# micro3.net
KiCad netlist of a schematic drawn in EAGLE
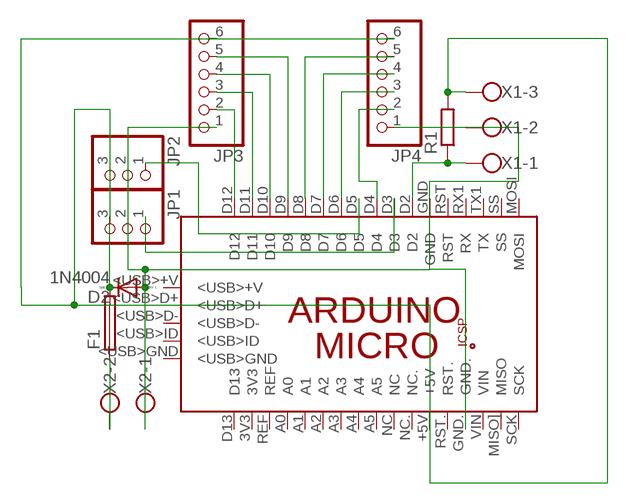
[diagram p0: schematic, sheet 1]

(export (version "E")
  (design (tool "Eeschema 10.0.6"))
  (components
    (comp (ref "D2")
      (value "1N4004")
      (footprint "eagle-import:DO41-10")
      (libsource (lib "eagle-import") (part "1N4004"))
    )
    (comp (ref "F1")
      (value "GSH15")
      (footprint "eagle-import:GSH15")
      (fields (field (name "MPN") "64900001039"))
      (libsource (lib "eagle-import") (part "GSH15"))
    )
    (comp (ref "JP1")
      (value "PINHD-1X3")
      (footprint "eagle-import:1X03")
      (libsource (lib "eagle-import") (part "PINHD-1X3"))
    )
    (comp (ref "JP2")
      (value "PINHD-1X3")
      (footprint "eagle-import:1X03")
      (libsource (lib "eagle-import") (part "PINHD-1X3"))
    )
    (comp (ref "JP3")
      (value "PINHD-1X6")
      (footprint "eagle-import:1X06")
      (libsource (lib "eagle-import") (part "PINHD-1X6"))
    )
    (comp (ref "JP4")
      (value "PINHD-1X6")
      (footprint "eagle-import:1X06")
      (libsource (lib "eagle-import") (part "PINHD-1X6"))
    )
    (comp (ref "PCB1")
      (value "ARDUINO_MICRO")
      (footprint "eagle-import:ARDUINO_MICRO")
      (libsource (lib "eagle-import") (part "ARDUINO_MICRO"))
    )
    (comp (ref "R1")
      (value "R-EU_0207/15")
      (footprint "eagle-import:0207_15")
      (libsource (lib "eagle-import") (part "R-EU_0207/15"))
    )
    (comp (ref "X1")
      (value "W237-103")
      (footprint "eagle-import:W237-103")
      (fields (field (name "MPN") "237-103"))
      (libsource (lib "eagle-import") (part "W237-103"))
    )
    (comp (ref "X2")
      (value "W237-102")
      (footprint "eagle-import:W237-102")
      (fields (field (name "MPN") "237-102"))
      (libsource (lib "eagle-import") (part "W237-102"))
    )
  )
  (nets
    (net (code "1") (name "Net-(JP1-Pad1)") (class "Default")
      (node (ref "JP1") (pin "1") (pinfunction "1_1") (pintype "passive"))
      (node (ref "PCB1") (pin "D3") (pinfunction "D3_D3") (pintype "bidirectional"))
    )
    (net (code "2") (name "Net-(JP2-Pad1)") (class "Default")
      (node (ref "JP2") (pin "1") (pinfunction "1_1") (pintype "passive"))
      (node (ref "PCB1") (pin "D5") (pinfunction "D5_D5") (pintype "bidirectional"))
    )
    (net (code "3") (name "Net-(JP3-Pad2)") (class "Default")
      (node (ref "JP3") (pin "2") (pinfunction "2_2") (pintype "passive"))
      (node (ref "PCB1") (pin "D12") (pinfunction "D12_D12") (pintype "bidirectional"))
    )
    (net (code "4") (name "Net-(JP3-Pad3)") (class "Default")
      (node (ref "JP3") (pin "3") (pinfunction "3_3") (pintype "passive"))
      (node (ref "PCB1") (pin "D11") (pinfunction "D11_D11") (pintype "bidirectional"))
    )
    (net (code "5") (name "Net-(JP3-Pad4)") (class "Default")
      (node (ref "JP3") (pin "4") (pinfunction "4_4") (pintype "passive"))
      (node (ref "PCB1") (pin "D10") (pinfunction "D10_D10") (pintype "bidirectional"))
    )
    (net (code "6") (name "Net-(JP3-Pad5)") (class "Default")
      (node (ref "JP3") (pin "5") (pinfunction "5_5") (pintype "passive"))
      (node (ref "PCB1") (pin "D9") (pinfunction "D9_D9") (pintype "bidirectional"))
    )
    (net (code "7") (name "Net-(JP4-Pad2)") (class "Default")
      (node (ref "JP4") (pin "2") (pinfunction "2_2") (pintype "passive"))
      (node (ref "PCB1") (pin "D4") (pinfunction "D4_D4") (pintype "bidirectional"))
    )
    (net (code "8") (name "Net-(JP4-Pad3)") (class "Default")
      (node (ref "JP4") (pin "3") (pinfunction "3_3") (pintype "passive"))
      (node (ref "PCB1") (pin "D6") (pinfunction "D6_D6") (pintype "bidirectional"))
    )
    (net (code "9") (name "Net-(JP4-Pad4)") (class "Default")
      (node (ref "JP4") (pin "4") (pinfunction "4_4") (pintype "passive"))
      (node (ref "PCB1") (pin "D7") (pinfunction "D7_D7") (pintype "bidirectional"))
    )
    (net (code "10") (name "Net-(JP4-Pad5)") (class "Default")
      (node (ref "JP4") (pin "5") (pinfunction "5_5") (pintype "passive"))
      (node (ref "PCB1") (pin "D8") (pinfunction "D8_D8") (pintype "bidirectional"))
    )
    (net (code "11") (name "Net-(X1A-KL)") (class "Default")
      (node (ref "PCB1") (pin "D2") (pinfunction "D2_D2") (pintype "bidirectional"))
      (node (ref "R1") (pin "1") (pinfunction "1_1") (pintype "passive"))
      (node (ref "X1") (pin "1") (pinfunction "KL_1") (pintype "passive"))
    )
    (net (code "12") (name "Net-(X1B-KL)") (class "Default")
      (node (ref "D2") (pin "A") (pinfunction "A_A") (pintype "passive"))
      (node (ref "JP1") (pin "2") (pinfunction "2_2") (pintype "passive"))
      (node (ref "JP2") (pin "2") (pinfunction "2_2") (pintype "passive"))
      (node (ref "JP3") (pin "1") (pinfunction "1_1") (pintype "passive"))
      (node (ref "JP4") (pin "1") (pinfunction "1_1") (pintype "passive"))
      (node (ref "PCB1") (pin "GND") (pinfunction "GND_GND") (pintype "bidirectional"))
      (node (ref "PCB1") (pin "GND.") (pinfunction "GND._GND.") (pintype "bidirectional"))
      (node (ref "X1") (pin "2") (pinfunction "KL_2") (pintype "passive"))
      (node (ref "X2") (pin "1") (pinfunction "KL_1") (pintype "passive"))
    )
    (net (code "13") (name "Net-(X1C-KL)") (class "Default")
      (node (ref "D2") (pin "C") (pinfunction "C_C") (pintype "passive"))
      (node (ref "F1") (pin "2") (pinfunction "2_2") (pintype "passive"))
      (node (ref "JP1") (pin "3") (pinfunction "3_3") (pintype "passive"))
      (node (ref "JP2") (pin "3") (pinfunction "3_3") (pintype "passive"))
      (node (ref "JP3") (pin "6") (pinfunction "6_6") (pintype "passive"))
      (node (ref "JP4") (pin "6") (pinfunction "6_6") (pintype "passive"))
      (node (ref "PCB1") (pin "+5V") (pinfunction "+5V_+5V") (pintype "bidirectional"))
      (node (ref "R1") (pin "2") (pinfunction "2_2") (pintype "passive"))
      (node (ref "X1") (pin "3") (pinfunction "KL_3") (pintype "passive"))
    )
    (net (code "14") (name "Net-(X2B-KL)") (class "Default")
      (node (ref "F1") (pin "1") (pinfunction "1_1") (pintype "passive"))
      (node (ref "X2") (pin "2") (pinfunction "KL_2") (pintype "passive"))
    )
    (net (code "15") (name "unconnected-(PCB1-MISO-PadMISO])") (class "Default")
      (node (ref "PCB1") (pin "MISO]") (pinfunction "MISO_MISO]") (pintype "bidirectional"))
    )
    (net (code "16") (name "unconnected-(PCB1-Pad3V3)") (class "Default")
      (node (ref "PCB1") (pin "3V3") (pinfunction "3V3_3V3") (pintype "bidirectional"))
    )
    (net (code "17") (name "unconnected-(PCB1-Pad5V)") (class "Default")
      (node (ref "PCB1") (pin "5V") (pinfunction "5V_5V") (pintype "bidirectional"))
    )
    (net (code "18") (name "unconnected-(PCB1-Pad<USB>+V)") (class "Default")
      (node (ref "PCB1") (pin "<USB>+V") (pinfunction "<USB>+V_<USB>+V") (pintype "bidirectional"))
    )
    (net (code "19") (name "unconnected-(PCB1-Pad<USB>D+)") (class "Default")
      (node (ref "PCB1") (pin "<USB>D+") (pinfunction "<USB>D+_<USB>D+") (pintype "bidirectional"))
    )
    (net (code "20") (name "unconnected-(PCB1-Pad<USB>D-)") (class "Default")
      (node (ref "PCB1") (pin "<USB>D-") (pinfunction "<USB>D-_<USB>D-") (pintype "bidirectional"))
    )
    (net (code "21") (name "unconnected-(PCB1-Pad<USB>GND)") (class "Default")
      (node (ref "PCB1") (pin "<USB>GND") (pinfunction "<USB>GND_<USB>GND") (pintype "bidirectional"))
    )
    (net (code "22") (name "unconnected-(PCB1-Pad<USB>ID)") (class "Default")
      (node (ref "PCB1") (pin "<USB>ID") (pinfunction "<USB>ID_<USB>ID") (pintype "bidirectional"))
    )
    (net (code "23") (name "unconnected-(PCB1-PadA0)") (class "Default")
      (node (ref "PCB1") (pin "A0") (pinfunction "A0_A0") (pintype "bidirectional"))
    )
    (net (code "24") (name "unconnected-(PCB1-PadA1)") (class "Default")
      (node (ref "PCB1") (pin "A1") (pinfunction "A1_A1") (pintype "bidirectional"))
    )
    (net (code "25") (name "unconnected-(PCB1-PadA2)") (class "Default")
      (node (ref "PCB1") (pin "A2") (pinfunction "A2_A2") (pintype "bidirectional"))
    )
    (net (code "26") (name "unconnected-(PCB1-PadA3)") (class "Default")
      (node (ref "PCB1") (pin "A3") (pinfunction "A3_A3") (pintype "bidirectional"))
    )
    (net (code "27") (name "unconnected-(PCB1-PadA4)") (class "Default")
      (node (ref "PCB1") (pin "A4") (pinfunction "A4_A4") (pintype "bidirectional"))
    )
    (net (code "28") (name "unconnected-(PCB1-PadA5)") (class "Default")
      (node (ref "PCB1") (pin "A5") (pinfunction "A5_A5") (pintype "bidirectional"))
    )
    (net (code "29") (name "unconnected-(PCB1-PadD13)") (class "Default")
      (node (ref "PCB1") (pin "D13") (pinfunction "D13_D13") (pintype "bidirectional"))
    )
    (net (code "30") (name "unconnected-(PCB1-PadGND_)") (class "Default")
      (node (ref "PCB1") (pin "GND_") (pinfunction "GND__GND_") (pintype "bidirectional"))
    )
    (net (code "31") (name "unconnected-(PCB1-PadMISO.)") (class "Default")
      (node (ref "PCB1") (pin "MISO.") (pinfunction "MISO._MISO.") (pintype "bidirectional"))
    )
    (net (code "32") (name "unconnected-(PCB1-PadMOSI)") (class "Default")
      (node (ref "PCB1") (pin "MOSI") (pinfunction "MOSI_MOSI") (pintype "bidirectional"))
    )
    (net (code "33") (name "unconnected-(PCB1-PadMOSI.)") (class "Default")
      (node (ref "PCB1") (pin "MOSI.") (pinfunction "MOSI._MOSI.") (pintype "bidirectional"))
    )
    (net (code "34") (name "unconnected-(PCB1-PadNC)") (class "Default")
      (node (ref "PCB1") (pin "NC") (pinfunction "NC_NC") (pintype "bidirectional"))
    )
    (net (code "35") (name "unconnected-(PCB1-PadNC.)") (class "Default")
      (node (ref "PCB1") (pin "NC.") (pinfunction "NC._NC.") (pintype "bidirectional"))
    )
    (net (code "36") (name "unconnected-(PCB1-PadREF)") (class "Default")
      (node (ref "PCB1") (pin "REF") (pinfunction "REF_REF") (pintype "bidirectional"))
    )
    (net (code "37") (name "unconnected-(PCB1-PadRESET..)") (class "Default")
      (node (ref "PCB1") (pin "RESET..") (pinfunction "RESET.._RESET..") (pintype "bidirectional"))
    )
    (net (code "38") (name "unconnected-(PCB1-PadRST)") (class "Default")
      (node (ref "PCB1") (pin "RST") (pinfunction "RST_RST") (pintype "bidirectional"))
    )
    (net (code "39") (name "unconnected-(PCB1-PadRST.)") (class "Default")
      (node (ref "PCB1") (pin "RST.") (pinfunction "RST._RST.") (pintype "bidirectional"))
    )
    (net (code "40") (name "unconnected-(PCB1-PadSCK)") (class "Default")
      (node (ref "PCB1") (pin "SCK") (pinfunction "SCK_SCK") (pintype "bidirectional"))
    )
    (net (code "41") (name "unconnected-(PCB1-PadSCK.)") (class "Default")
      (node (ref "PCB1") (pin "SCK.") (pinfunction "SCK._SCK.") (pintype "bidirectional"))
    )
    (net (code "42") (name "unconnected-(PCB1-PadSS)") (class "Default")
      (node (ref "PCB1") (pin "SS") (pinfunction "SS_SS") (pintype "bidirectional"))
    )
    (net (code "43") (name "unconnected-(PCB1-PadVIN)") (class "Default")
      (node (ref "PCB1") (pin "VIN") (pinfunction "VIN_VIN") (pintype "bidirectional"))
    )
    (net (code "44") (name "unconnected-(PCB1-RX-PadRX1)") (class "Default")
      (node (ref "PCB1") (pin "RX1") (pinfunction "RX_RX1") (pintype "bidirectional"))
    )
    (net (code "45") (name "unconnected-(PCB1-TX-PadTX1)") (class "Default")
      (node (ref "PCB1") (pin "TX1") (pinfunction "TX_TX1") (pintype "bidirectional"))
    )
  )
)
